# uzed-hmdi.net
KiCad netlist of a schematic drawn in EAGLE
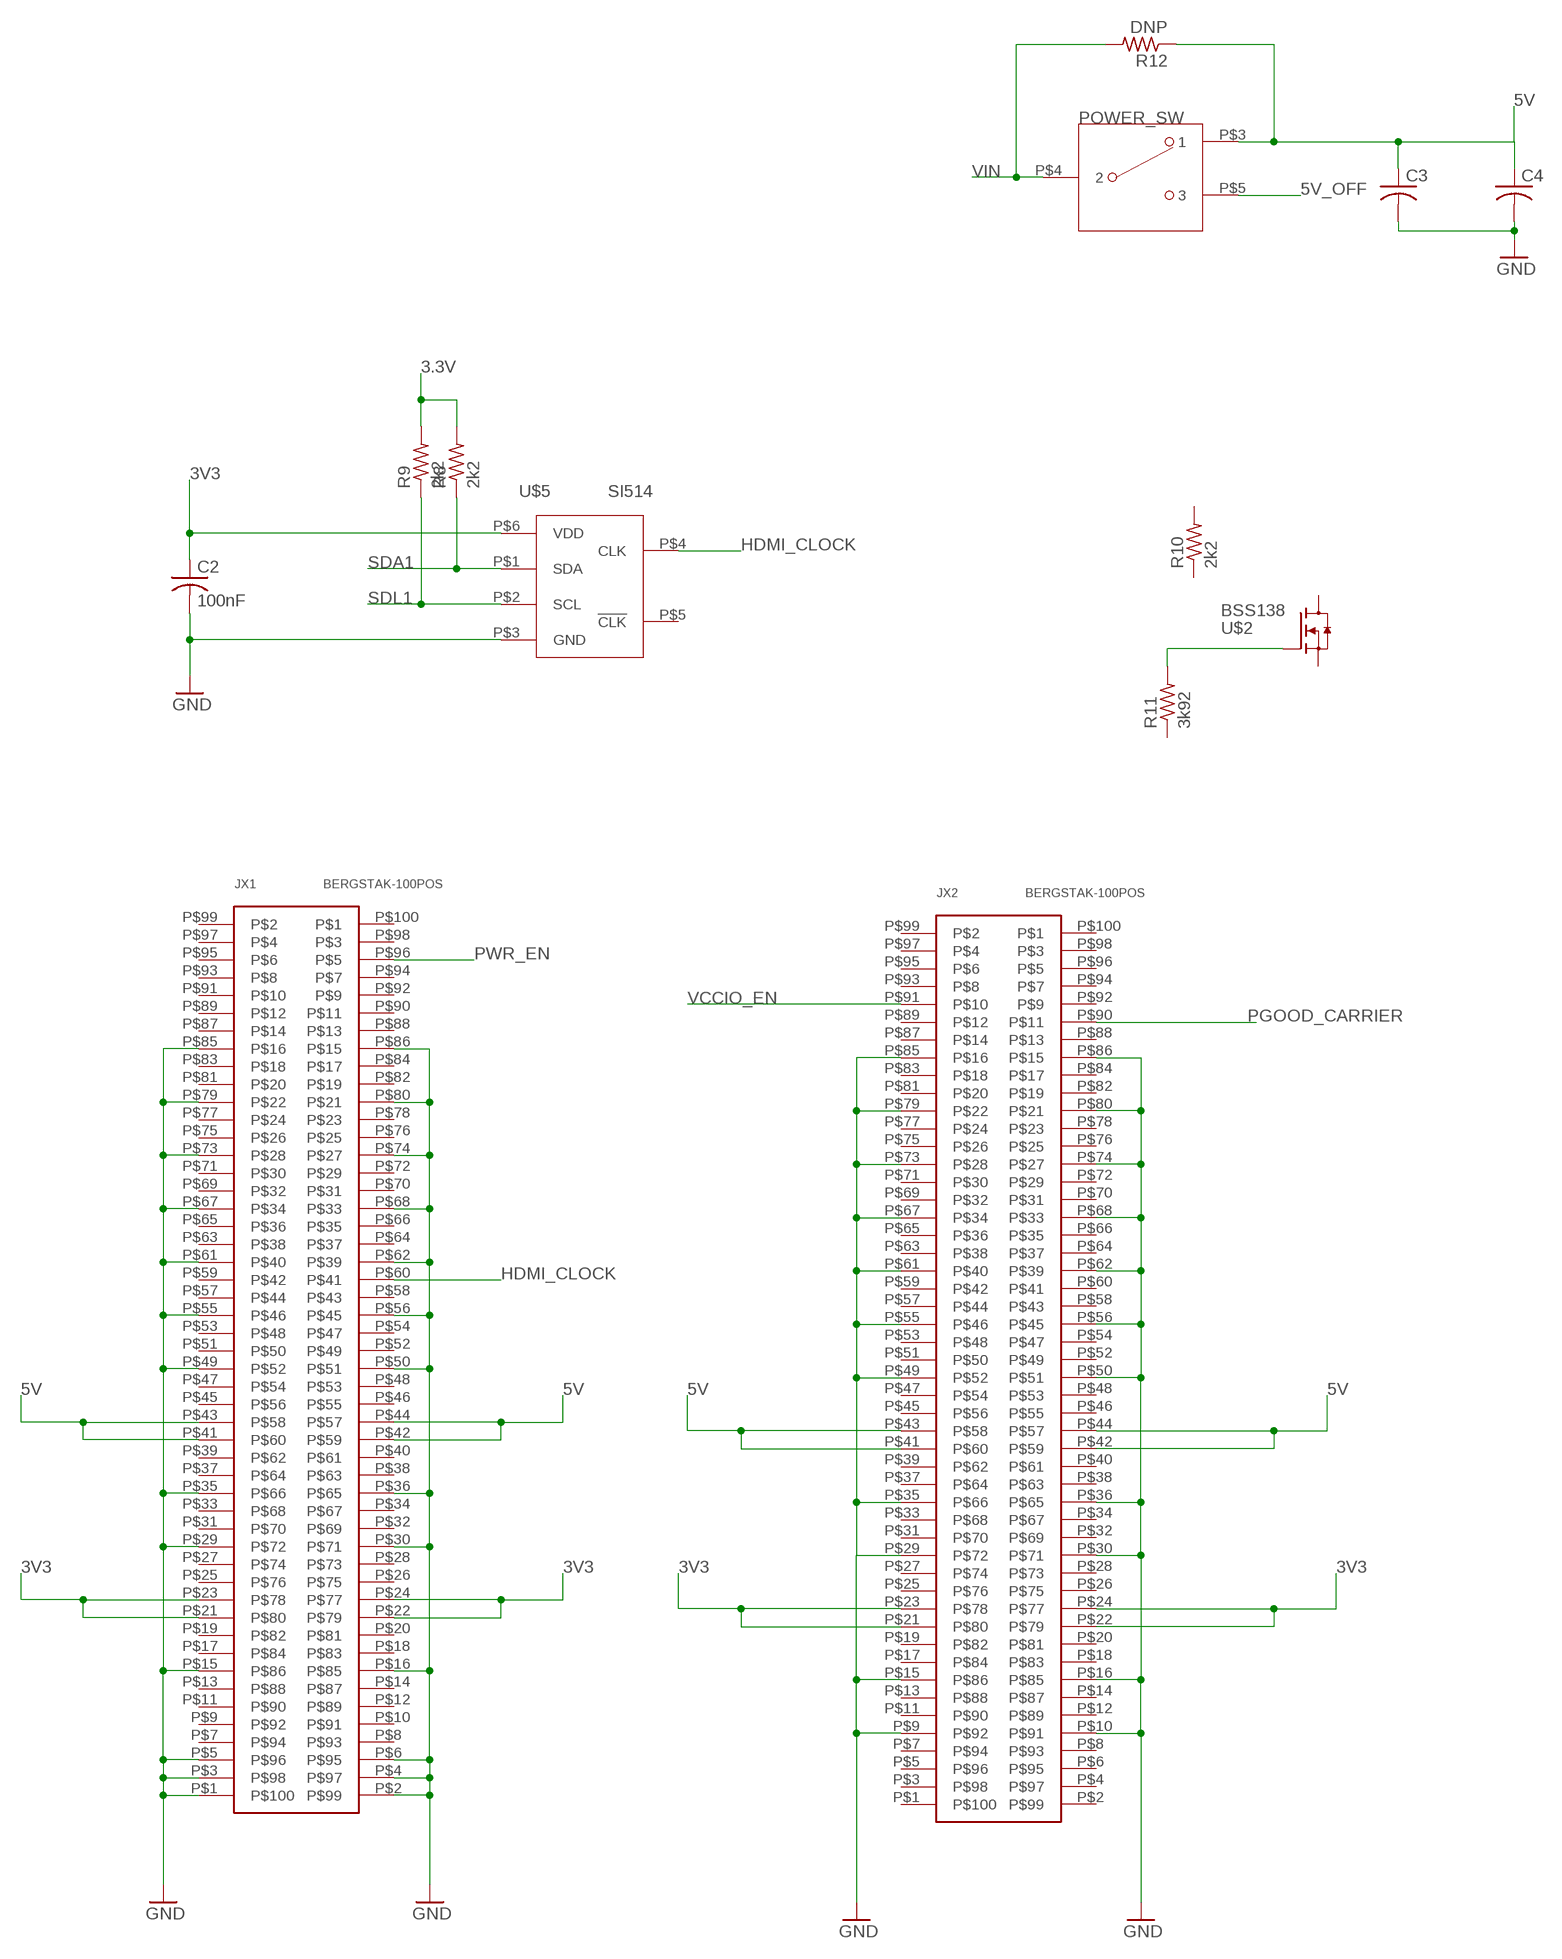
[diagram p0: schematic, sheet 1]
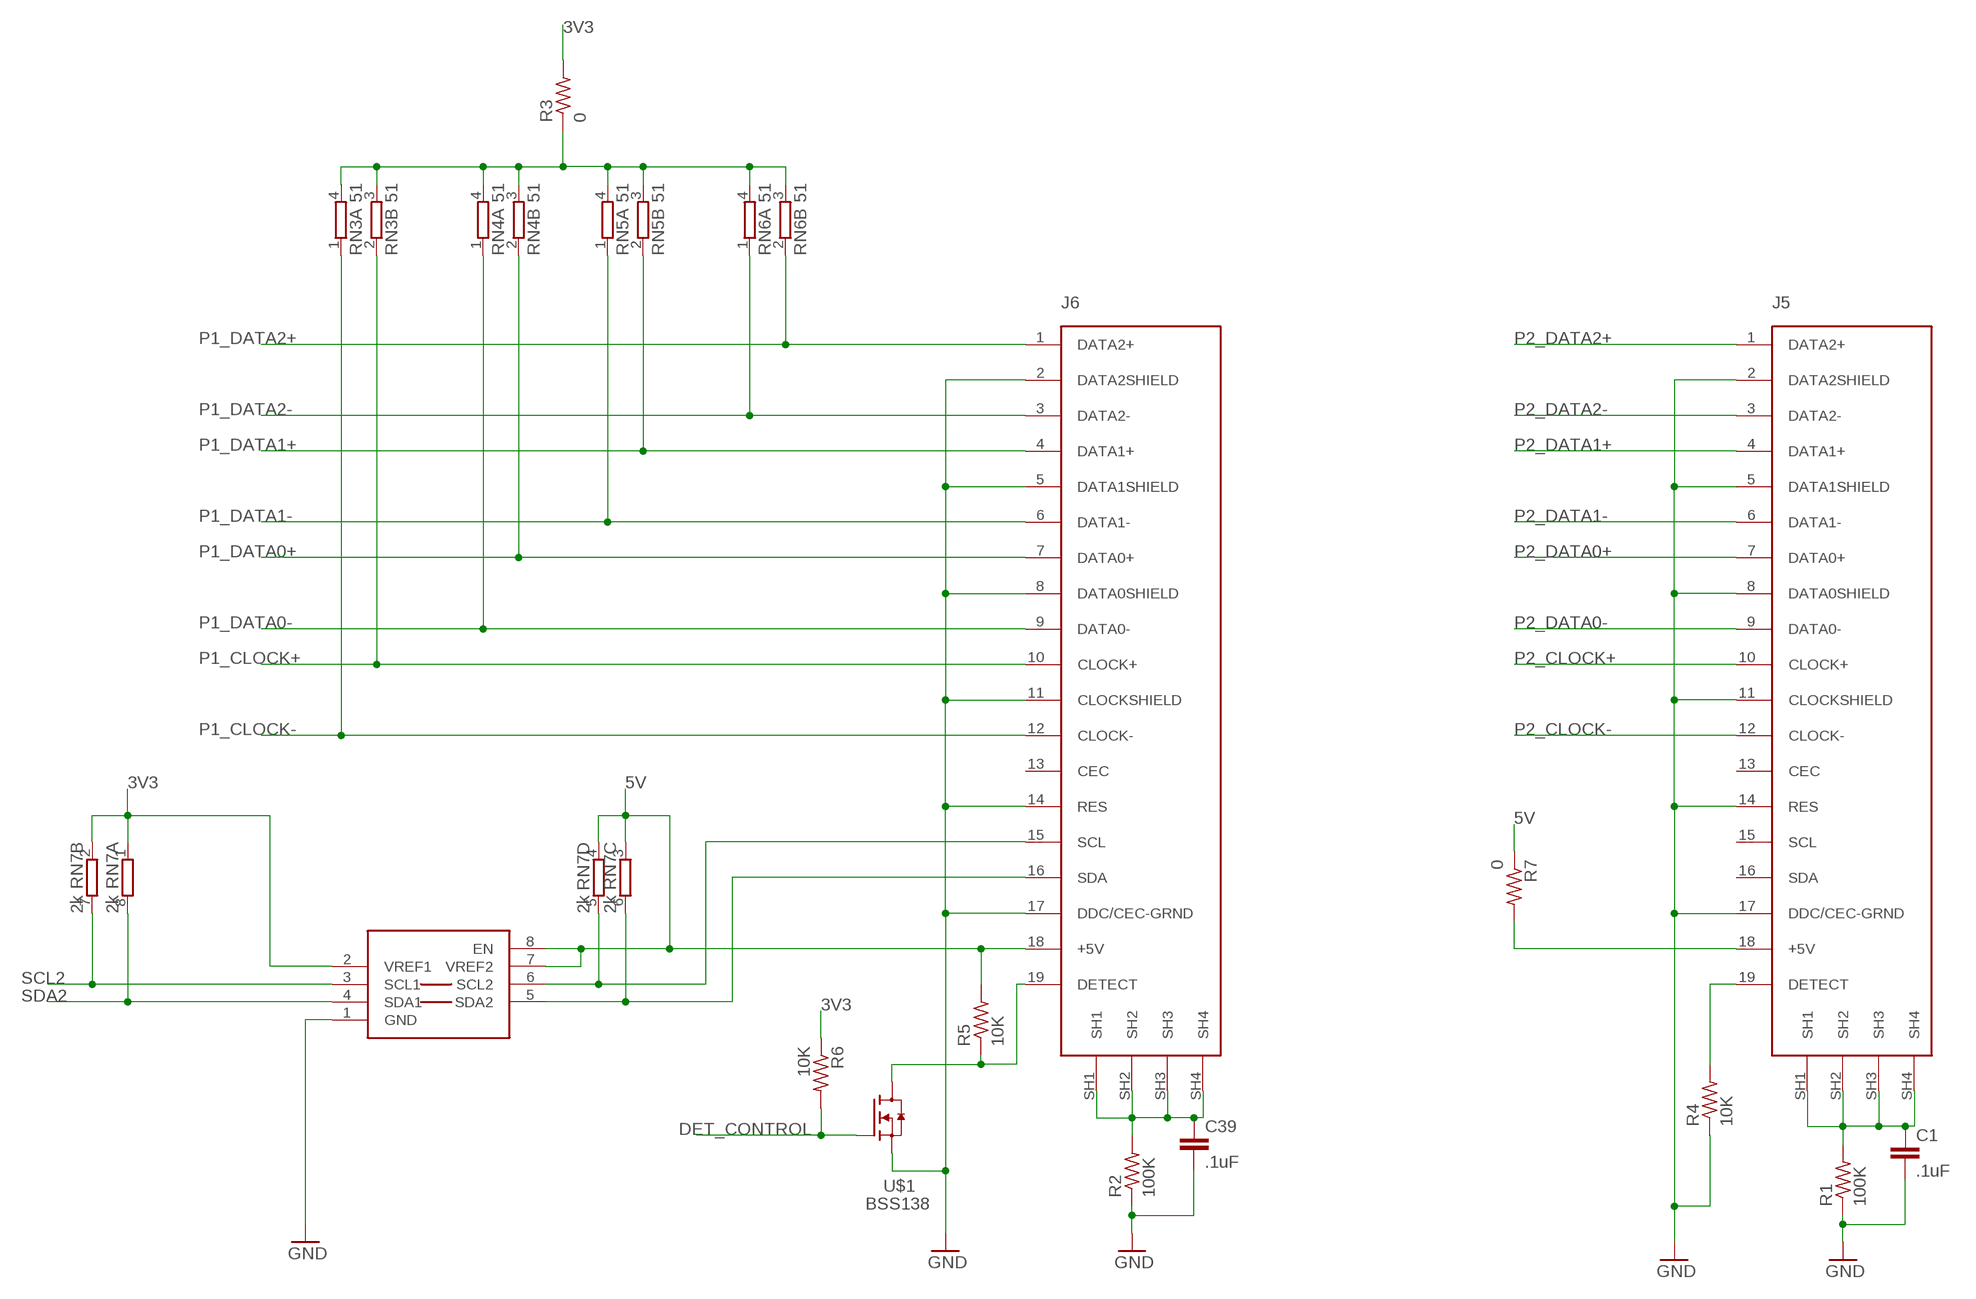
[diagram p1: schematic, sheet 2]

(export (version "E")
  (design (tool "Eeschema 10.0.6"))
  (components
    (comp (ref "C2")
      (value "100nF")
      (footprint "eagle-import:C0603")
      (libsource (lib "eagle-import") (part "C-USC0603"))
    )
    (comp (ref "C3")
      (value "C-USC0603")
      (footprint "eagle-import:C0603")
      (libsource (lib "eagle-import") (part "C-USC0603"))
    )
    (comp (ref "C4")
      (value "C-USC1206K")
      (footprint "eagle-import:C1206K")
      (libsource (lib "eagle-import") (part "C-USC1206K"))
    )
    (comp (ref "JX1")
      (value "BERGSTAK-100POS")
      (footprint "eagle-import:BERG100POS")
      (libsource (lib "eagle-import") (part "BERGSTAK-100POS"))
    )
    (comp (ref "JX2")
      (value "BERGSTAK-100POS")
      (footprint "eagle-import:BERG100POS")
      (libsource (lib "eagle-import") (part "BERGSTAK-100POS"))
    )
    (comp (ref "POWER_SW")
      (value "T511006")
      (footprint "eagle-import:SPDT")
      (libsource (lib "eagle-import") (part "T511006"))
    )
    (comp (ref "R8")
      (value "2k2")
      (footprint "eagle-import:R0603")
      (libsource (lib "eagle-import") (part "rcl_334_R-US_R0603"))
    )
    (comp (ref "R9")
      (value "2k2")
      (footprint "eagle-import:R0603")
      (libsource (lib "eagle-import") (part "rcl_334_R-US_R0603"))
    )
    (comp (ref "R10")
      (value "2k2")
      (footprint "eagle-import:R0603")
      (libsource (lib "eagle-import") (part "rcl_334_R-US_R0603"))
    )
    (comp (ref "R11")
      (value "3k92")
      (footprint "eagle-import:R0603")
      (libsource (lib "eagle-import") (part "rcl_334_R-US_R0603"))
    )
    (comp (ref "R12")
      (value "DNP")
      (footprint "eagle-import:R0603")
      (libsource (lib "eagle-import") (part "rcl_334_R-US_R0603"))
    )
    (comp (ref "U$2")
      (value "BSS138")
      (footprint "eagle-import:SOT23")
      (libsource (lib "eagle-import") (part "BSS138"))
    )
    (comp (ref "U$5")
      (value "SI514")
      (footprint "eagle-import:XTAL-6PIN")
      (libsource (lib "eagle-import") (part "SI514"))
    )
    (comp (ref "C1")
      (value ".1uF")
      (footprint "eagle-import:C0603K")
      (libsource (lib "eagle-import") (part "C-EUC0603K"))
    )
    (comp (ref "C39")
      (value ".1uF")
      (footprint "eagle-import:C0603K")
      (libsource (lib "eagle-import") (part "C-EUC0603K"))
    )
    (comp (ref "J5")
      (value "HDMI-TYPE-A-RECEPTICALFCI10029449")
      (footprint "eagle-import:FCI-HDMI-TYPE-A-RECEPT")
      (libsource (lib "eagle-import") (part "HDMI-TYPE-A-RECEPTICALFCI10029449"))
    )
    (comp (ref "J6")
      (value "HDMI-TYPE-A-RECEPTICALFCI10029449")
      (footprint "eagle-import:FCI-HDMI-TYPE-A-RECEPT")
      (libsource (lib "eagle-import") (part "HDMI-TYPE-A-RECEPTICALFCI10029449"))
    )
    (comp (ref "PCA9306")
      (value "PCA9306")
      (footprint "eagle-import:PSOP-8")
      (libsource (lib "eagle-import") (part "PCA9306"))
    )
    (comp (ref "R1")
      (value "100K")
      (footprint "eagle-import:R0603")
      (libsource (lib "eagle-import") (part "R-US_R0603"))
    )
    (comp (ref "R2")
      (value "100K")
      (footprint "eagle-import:R0603")
      (libsource (lib "eagle-import") (part "R-US_R0603"))
    )
    (comp (ref "R3")
      (value "0")
      (footprint "eagle-import:R0603")
      (libsource (lib "eagle-import") (part "rcl_334_R-US_R0603"))
    )
    (comp (ref "R4")
      (value "10K")
      (footprint "eagle-import:R0603")
      (libsource (lib "eagle-import") (part "R-US_R0603"))
    )
    (comp (ref "R5")
      (value "10K")
      (footprint "eagle-import:R0603")
      (libsource (lib "eagle-import") (part "R-US_R0603"))
    )
    (comp (ref "R6")
      (value "10K")
      (footprint "eagle-import:R0603")
      (libsource (lib "eagle-import") (part "R-US_R0603"))
    )
    (comp (ref "R7")
      (value "0")
      (footprint "eagle-import:R0603")
      (libsource (lib "eagle-import") (part "R-US_R0603"))
    )
    (comp (ref "RN3")
      (value "51")
      (footprint "eagle-import:EXB34V")
      (libsource (lib "eagle-import") (part "2R-NEXB34V"))
    )
    (comp (ref "RN4")
      (value "51")
      (footprint "eagle-import:EXB34V")
      (libsource (lib "eagle-import") (part "2R-NEXB34V"))
    )
    (comp (ref "RN5")
      (value "51")
      (footprint "eagle-import:EXB34V")
      (libsource (lib "eagle-import") (part "2R-NEXB34V"))
    )
    (comp (ref "RN6")
      (value "51")
      (footprint "eagle-import:EXB34V")
      (libsource (lib "eagle-import") (part "2R-NEXB34V"))
    )
    (comp (ref "RN7")
      (value "2k")
      (footprint "eagle-import:0603-ARV")
      (libsource (lib "eagle-import") (part "4R-N0603-ARV"))
    )
    (comp (ref "U$1")
      (value "BSS138")
      (footprint "eagle-import:SOT23")
      (libsource (lib "eagle-import") (part "BSS138"))
    )
  )
  (nets
    (net (code "1") (name "3.3V") (class "Default")
      (node (ref "R8") (pin "2") (pinfunction "2_2") (pintype "passive"))
      (node (ref "R9") (pin "2") (pinfunction "2_2") (pintype "passive"))
    )
    (net (code "2") (name "3V3") (class "Default")
      (node (ref "C2") (pin "1") (pinfunction "1_1") (pintype "passive"))
      (node (ref "JX1") (pin "P$21") (pinfunction "P$80_P$21") (pintype "bidirectional"))
      (node (ref "JX1") (pin "P$22") (pinfunction "P$79_P$22") (pintype "bidirectional"))
      (node (ref "JX1") (pin "P$23") (pinfunction "P$78_P$23") (pintype "bidirectional"))
      (node (ref "JX1") (pin "P$24") (pinfunction "P$77_P$24") (pintype "bidirectional"))
      (node (ref "JX2") (pin "P$21") (pinfunction "P$80_P$21") (pintype "bidirectional"))
      (node (ref "JX2") (pin "P$22") (pinfunction "P$79_P$22") (pintype "bidirectional"))
      (node (ref "JX2") (pin "P$23") (pinfunction "P$78_P$23") (pintype "bidirectional"))
      (node (ref "JX2") (pin "P$24") (pinfunction "P$77_P$24") (pintype "bidirectional"))
      (node (ref "PCA9306") (pin "2") (pinfunction "VREF1_2") (pintype "bidirectional"))
      (node (ref "R3") (pin "2") (pinfunction "2_2") (pintype "passive"))
      (node (ref "R6") (pin "1") (pinfunction "1_1") (pintype "passive"))
      (node (ref "RN7") (pin "1") (pinfunction "1_1") (pintype "passive"))
      (node (ref "RN7") (pin "2") (pinfunction "1_2") (pintype "passive"))
      (node (ref "U$5") (pin "P$6") (pinfunction "VDD_P$6") (pintype "bidirectional"))
    )
    (net (code "3") (name "5V") (class "Default")
      (node (ref "C3") (pin "1") (pinfunction "1_1") (pintype "passive"))
      (node (ref "C4") (pin "1") (pinfunction "1_1") (pintype "passive"))
      (node (ref "J6") (pin "18") (pinfunction "+5V_18") (pintype "bidirectional"))
      (node (ref "JX1") (pin "P$41") (pinfunction "P$60_P$41") (pintype "bidirectional"))
      (node (ref "JX1") (pin "P$42") (pinfunction "P$59_P$42") (pintype "bidirectional"))
      (node (ref "JX1") (pin "P$43") (pinfunction "P$58_P$43") (pintype "bidirectional"))
      (node (ref "JX1") (pin "P$44") (pinfunction "P$57_P$44") (pintype "bidirectional"))
      (node (ref "JX2") (pin "P$41") (pinfunction "P$60_P$41") (pintype "bidirectional"))
      (node (ref "JX2") (pin "P$42") (pinfunction "P$59_P$42") (pintype "bidirectional"))
      (node (ref "JX2") (pin "P$43") (pinfunction "P$58_P$43") (pintype "bidirectional"))
      (node (ref "JX2") (pin "P$44") (pinfunction "P$57_P$44") (pintype "bidirectional"))
      (node (ref "PCA9306") (pin "7") (pinfunction "VREF2_7") (pintype "bidirectional"))
      (node (ref "PCA9306") (pin "8") (pinfunction "EN_8") (pintype "bidirectional"))
      (node (ref "POWER_SW") (pin "P$3") (pinfunction "1_P$3") (pintype "bidirectional"))
      (node (ref "R12") (pin "1") (pinfunction "1_1") (pintype "passive"))
      (node (ref "R5") (pin "2") (pinfunction "2_2") (pintype "passive"))
      (node (ref "R7") (pin "1") (pinfunction "1_1") (pintype "passive"))
      (node (ref "RN7") (pin "3") (pinfunction "1_3") (pintype "passive"))
      (node (ref "RN7") (pin "4") (pinfunction "1_4") (pintype "passive"))
    )
    (net (code "4") (name "5V_OFF") (class "Default")
      (node (ref "POWER_SW") (pin "P$5") (pinfunction "3_P$5") (pintype "bidirectional"))
    )
    (net (code "5") (name "DET_CONTROL") (class "Default")
      (node (ref "R6") (pin "2") (pinfunction "2_2") (pintype "passive"))
      (node (ref "U$1") (pin "1") (pinfunction "G_1") (pintype "passive"))
    )
    (net (code "6") (name "GND") (class "Default")
      (node (ref "C1") (pin "2") (pinfunction "2_2") (pintype "passive"))
      (node (ref "C2") (pin "2") (pinfunction "2_2") (pintype "passive"))
      (node (ref "C3") (pin "2") (pinfunction "2_2") (pintype "passive"))
      (node (ref "C39") (pin "2") (pinfunction "2_2") (pintype "passive"))
      (node (ref "C4") (pin "2") (pinfunction "2_2") (pintype "passive"))
      (node (ref "J5") (pin "11") (pinfunction "CLOCKSHIELD_11") (pintype "bidirectional"))
      (node (ref "J5") (pin "14") (pinfunction "RES_14") (pintype "bidirectional"))
      (node (ref "J5") (pin "17") (pinfunction "DDC/CEC-GRND_17") (pintype "bidirectional"))
      (node (ref "J5") (pin "2") (pinfunction "DATA2SHIELD_2") (pintype "bidirectional"))
      (node (ref "J5") (pin "5") (pinfunction "DATA1SHIELD_5") (pintype "bidirectional"))
      (node (ref "J5") (pin "8") (pinfunction "DATA0SHIELD_8") (pintype "bidirectional"))
      (node (ref "J6") (pin "11") (pinfunction "CLOCKSHIELD_11") (pintype "bidirectional"))
      (node (ref "J6") (pin "14") (pinfunction "RES_14") (pintype "bidirectional"))
      (node (ref "J6") (pin "17") (pinfunction "DDC/CEC-GRND_17") (pintype "bidirectional"))
      (node (ref "J6") (pin "2") (pinfunction "DATA2SHIELD_2") (pintype "bidirectional"))
      (node (ref "J6") (pin "5") (pinfunction "DATA1SHIELD_5") (pintype "bidirectional"))
      (node (ref "J6") (pin "8") (pinfunction "DATA0SHIELD_8") (pintype "bidirectional"))
      (node (ref "JX1") (pin "P$1") (pinfunction "P$100_P$1") (pintype "bidirectional"))
      (node (ref "JX1") (pin "P$15") (pinfunction "P$86_P$15") (pintype "bidirectional"))
      (node (ref "JX1") (pin "P$16") (pinfunction "P$85_P$16") (pintype "bidirectional"))
      (node (ref "JX1") (pin "P$2") (pinfunction "P$99_P$2") (pintype "bidirectional"))
      (node (ref "JX1") (pin "P$29") (pinfunction "P$72_P$29") (pintype "bidirectional"))
      (node (ref "JX1") (pin "P$3") (pinfunction "P$98_P$3") (pintype "bidirectional"))
      (node (ref "JX1") (pin "P$30") (pinfunction "P$71_P$30") (pintype "bidirectional"))
      (node (ref "JX1") (pin "P$35") (pinfunction "P$66_P$35") (pintype "bidirectional"))
      (node (ref "JX1") (pin "P$36") (pinfunction "P$65_P$36") (pintype "bidirectional"))
      (node (ref "JX1") (pin "P$4") (pinfunction "P$97_P$4") (pintype "bidirectional"))
      (node (ref "JX1") (pin "P$49") (pinfunction "P$52_P$49") (pintype "bidirectional"))
      (node (ref "JX1") (pin "P$5") (pinfunction "P$96_P$5") (pintype "bidirectional"))
      (node (ref "JX1") (pin "P$50") (pinfunction "P$51_P$50") (pintype "bidirectional"))
      (node (ref "JX1") (pin "P$55") (pinfunction "P$46_P$55") (pintype "bidirectional"))
      (node (ref "JX1") (pin "P$56") (pinfunction "P$45_P$56") (pintype "bidirectional"))
      (node (ref "JX1") (pin "P$6") (pinfunction "P$95_P$6") (pintype "bidirectional"))
      (node (ref "JX1") (pin "P$61") (pinfunction "P$40_P$61") (pintype "bidirectional"))
      (node (ref "JX1") (pin "P$62") (pinfunction "P$39_P$62") (pintype "bidirectional"))
      (node (ref "JX1") (pin "P$67") (pinfunction "P$34_P$67") (pintype "bidirectional"))
      (node (ref "JX1") (pin "P$68") (pinfunction "P$33_P$68") (pintype "bidirectional"))
      (node (ref "JX1") (pin "P$73") (pinfunction "P$28_P$73") (pintype "bidirectional"))
      (node (ref "JX1") (pin "P$74") (pinfunction "P$27_P$74") (pintype "bidirectional"))
      (node (ref "JX1") (pin "P$79") (pinfunction "P$22_P$79") (pintype "bidirectional"))
      (node (ref "JX1") (pin "P$80") (pinfunction "P$21_P$80") (pintype "bidirectional"))
      (node (ref "JX1") (pin "P$85") (pinfunction "P$16_P$85") (pintype "bidirectional"))
      (node (ref "JX1") (pin "P$86") (pinfunction "P$15_P$86") (pintype "bidirectional"))
      (node (ref "JX2") (pin "P$10") (pinfunction "P$91_P$10") (pintype "bidirectional"))
      (node (ref "JX2") (pin "P$15") (pinfunction "P$86_P$15") (pintype "bidirectional"))
      (node (ref "JX2") (pin "P$16") (pinfunction "P$85_P$16") (pintype "bidirectional"))
      (node (ref "JX2") (pin "P$29") (pinfunction "P$72_P$29") (pintype "bidirectional"))
      (node (ref "JX2") (pin "P$30") (pinfunction "P$71_P$30") (pintype "bidirectional"))
      (node (ref "JX2") (pin "P$35") (pinfunction "P$66_P$35") (pintype "bidirectional"))
      (node (ref "JX2") (pin "P$36") (pinfunction "P$65_P$36") (pintype "bidirectional"))
      (node (ref "JX2") (pin "P$49") (pinfunction "P$52_P$49") (pintype "bidirectional"))
      (node (ref "JX2") (pin "P$50") (pinfunction "P$51_P$50") (pintype "bidirectional"))
      (node (ref "JX2") (pin "P$55") (pinfunction "P$46_P$55") (pintype "bidirectional"))
      (node (ref "JX2") (pin "P$56") (pinfunction "P$45_P$56") (pintype "bidirectional"))
      (node (ref "JX2") (pin "P$61") (pinfunction "P$40_P$61") (pintype "bidirectional"))
      (node (ref "JX2") (pin "P$62") (pinfunction "P$39_P$62") (pintype "bidirectional"))
      (node (ref "JX2") (pin "P$67") (pinfunction "P$34_P$67") (pintype "bidirectional"))
      (node (ref "JX2") (pin "P$68") (pinfunction "P$33_P$68") (pintype "bidirectional"))
      (node (ref "JX2") (pin "P$73") (pinfunction "P$28_P$73") (pintype "bidirectional"))
      (node (ref "JX2") (pin "P$74") (pinfunction "P$27_P$74") (pintype "bidirectional"))
      (node (ref "JX2") (pin "P$79") (pinfunction "P$22_P$79") (pintype "bidirectional"))
      (node (ref "JX2") (pin "P$80") (pinfunction "P$21_P$80") (pintype "bidirectional"))
      (node (ref "JX2") (pin "P$85") (pinfunction "P$16_P$85") (pintype "bidirectional"))
      (node (ref "JX2") (pin "P$86") (pinfunction "P$15_P$86") (pintype "bidirectional"))
      (node (ref "JX2") (pin "P$9") (pinfunction "P$92_P$9") (pintype "bidirectional"))
      (node (ref "PCA9306") (pin "1") (pinfunction "GND_1") (pintype "bidirectional"))
      (node (ref "R1") (pin "1") (pinfunction "1_1") (pintype "passive"))
      (node (ref "R2") (pin "1") (pinfunction "1_1") (pintype "passive"))
      (node (ref "R4") (pin "1") (pinfunction "1_1") (pintype "passive"))
      (node (ref "U$1") (pin "2") (pinfunction "S_2") (pintype "passive"))
      (node (ref "U$5") (pin "P$3") (pinfunction "GND_P$3") (pintype "bidirectional"))
    )
    (net (code "7") (name "HDMI_CLOCK") (class "Default")
      (node (ref "JX1") (pin "P$60") (pinfunction "P$41_P$60") (pintype "bidirectional"))
      (node (ref "U$5") (pin "P$4") (pinfunction "CLK_P$4") (pintype "bidirectional"))
    )
    (net (code "8") (name "Net-(C1-Pad1)") (class "Default")
      (node (ref "C1") (pin "1") (pinfunction "1_1") (pintype "passive"))
      (node (ref "J5") (pin "SH1") (pinfunction "SH1_SH1") (pintype "bidirectional"))
      (node (ref "J5") (pin "SH2") (pinfunction "SH2_SH2") (pintype "bidirectional"))
      (node (ref "J5") (pin "SH3") (pinfunction "SH3_SH3") (pintype "bidirectional"))
      (node (ref "J5") (pin "SH4") (pinfunction "SH4_SH4") (pintype "bidirectional"))
      (node (ref "R1") (pin "2") (pinfunction "2_2") (pintype "passive"))
    )
    (net (code "9") (name "Net-(C39-Pad1)") (class "Default")
      (node (ref "C39") (pin "1") (pinfunction "1_1") (pintype "passive"))
      (node (ref "J6") (pin "SH1") (pinfunction "SH1_SH1") (pintype "bidirectional"))
      (node (ref "J6") (pin "SH2") (pinfunction "SH2_SH2") (pintype "bidirectional"))
      (node (ref "J6") (pin "SH3") (pinfunction "SH3_SH3") (pintype "bidirectional"))
      (node (ref "J6") (pin "SH4") (pinfunction "SH4_SH4") (pintype "bidirectional"))
      (node (ref "R2") (pin "2") (pinfunction "2_2") (pintype "passive"))
    )
    (net (code "10") (name "Net-(J5-+5V)") (class "Default")
      (node (ref "J5") (pin "18") (pinfunction "+5V_18") (pintype "bidirectional"))
      (node (ref "R7") (pin "2") (pinfunction "2_2") (pintype "passive"))
    )
    (net (code "11") (name "Net-(J5-DETECT)") (class "Default")
      (node (ref "J5") (pin "19") (pinfunction "DETECT_19") (pintype "bidirectional"))
      (node (ref "R4") (pin "2") (pinfunction "2_2") (pintype "passive"))
    )
    (net (code "12") (name "Net-(J6-DETECT)") (class "Default")
      (node (ref "J6") (pin "19") (pinfunction "DETECT_19") (pintype "bidirectional"))
      (node (ref "R5") (pin "1") (pinfunction "1_1") (pintype "passive"))
      (node (ref "U$1") (pin "3") (pinfunction "D_3") (pintype "passive"))
    )
    (net (code "13") (name "Net-(J6-SCL)") (class "Default")
      (node (ref "J6") (pin "15") (pinfunction "SCL_15") (pintype "bidirectional"))
      (node (ref "PCA9306") (pin "6") (pinfunction "SCL2_6") (pintype "bidirectional"))
      (node (ref "RN7") (pin "5") (pinfunction "2_5") (pintype "passive"))
    )
    (net (code "14") (name "Net-(J6-SDA)") (class "Default")
      (node (ref "J6") (pin "16") (pinfunction "SDA_16") (pintype "bidirectional"))
      (node (ref "PCA9306") (pin "5") (pinfunction "SDA2_5") (pintype "bidirectional"))
      (node (ref "RN7") (pin "6") (pinfunction "2_6") (pintype "passive"))
    )
    (net (code "15") (name "Net-(RN3A-2)") (class "Default")
      (node (ref "R3") (pin "1") (pinfunction "1_1") (pintype "passive"))
      (node (ref "RN3") (pin "3") (pinfunction "2_3") (pintype "passive"))
      (node (ref "RN3") (pin "4") (pinfunction "2_4") (pintype "passive"))
      (node (ref "RN4") (pin "3") (pinfunction "2_3") (pintype "passive"))
      (node (ref "RN4") (pin "4") (pinfunction "2_4") (pintype "passive"))
      (node (ref "RN5") (pin "3") (pinfunction "2_3") (pintype "passive"))
      (node (ref "RN5") (pin "4") (pinfunction "2_4") (pintype "passive"))
      (node (ref "RN6") (pin "3") (pinfunction "2_3") (pintype "passive"))
      (node (ref "RN6") (pin "4") (pinfunction "2_4") (pintype "passive"))
    )
    (net (code "16") (name "Net-(U$2-G)") (class "Default")
      (node (ref "R11") (pin "2") (pinfunction "2_2") (pintype "passive"))
      (node (ref "U$2") (pin "1") (pinfunction "G_1") (pintype "passive"))
    )
    (net (code "17") (name "P1_CLOCK+") (class "Default")
      (node (ref "J6") (pin "10") (pinfunction "CLOCK+_10") (pintype "bidirectional"))
      (node (ref "RN3") (pin "2") (pinfunction "1_2") (pintype "passive"))
    )
    (net (code "18") (name "P1_CLOCK-") (class "Default")
      (node (ref "J6") (pin "12") (pinfunction "CLOCK-_12") (pintype "bidirectional"))
      (node (ref "RN3") (pin "1") (pinfunction "1_1") (pintype "passive"))
    )
    (net (code "19") (name "P1_DATA0+") (class "Default")
      (node (ref "J6") (pin "7") (pinfunction "DATA0+_7") (pintype "bidirectional"))
      (node (ref "RN4") (pin "2") (pinfunction "1_2") (pintype "passive"))
    )
    (net (code "20") (name "P1_DATA0-") (class "Default")
      (node (ref "J6") (pin "9") (pinfunction "DATA0-_9") (pintype "bidirectional"))
      (node (ref "RN4") (pin "1") (pinfunction "1_1") (pintype "passive"))
    )
    (net (code "21") (name "P1_DATA1+") (class "Default")
      (node (ref "J6") (pin "4") (pinfunction "DATA1+_4") (pintype "bidirectional"))
      (node (ref "RN5") (pin "2") (pinfunction "1_2") (pintype "passive"))
    )
    (net (code "22") (name "P1_DATA1-") (class "Default")
      (node (ref "J6") (pin "6") (pinfunction "DATA1-_6") (pintype "bidirectional"))
      (node (ref "RN5") (pin "1") (pinfunction "1_1") (pintype "passive"))
    )
    (net (code "23") (name "P1_DATA2+") (class "Default")
      (node (ref "J6") (pin "1") (pinfunction "DATA2+_1") (pintype "bidirectional"))
      (node (ref "RN6") (pin "2") (pinfunction "1_2") (pintype "passive"))
    )
    (net (code "24") (name "P1_DATA2-") (class "Default")
      (node (ref "J6") (pin "3") (pinfunction "DATA2-_3") (pintype "bidirectional"))
      (node (ref "RN6") (pin "1") (pinfunction "1_1") (pintype "passive"))
    )
    (net (code "25") (name "P2_CLOCK+") (class "Default")
      (node (ref "J5") (pin "10") (pinfunction "CLOCK+_10") (pintype "bidirectional"))
    )
    (net (code "26") (name "P2_CLOCK-") (class "Default")
      (node (ref "J5") (pin "12") (pinfunction "CLOCK-_12") (pintype "bidirectional"))
    )
    (net (code "27") (name "P2_DATA0+") (class "Default")
      (node (ref "J5") (pin "7") (pinfunction "DATA0+_7") (pintype "bidirectional"))
    )
    (net (code "28") (name "P2_DATA0-") (class "Default")
      (node (ref "J5") (pin "9") (pinfunction "DATA0-_9") (pintype "bidirectional"))
    )
    (net (code "29") (name "P2_DATA1+") (class "Default")
      (node (ref "J5") (pin "4") (pinfunction "DATA1+_4") (pintype "bidirectional"))
    )
    (net (code "30") (name "P2_DATA1-") (class "Default")
      (node (ref "J5") (pin "6") (pinfunction "DATA1-_6") (pintype "bidirectional"))
    )
    (net (code "31") (name "P2_DATA2+") (class "Default")
      (node (ref "J5") (pin "1") (pinfunction "DATA2+_1") (pintype "bidirectional"))
    )
    (net (code "32") (name "P2_DATA2-") (class "Default")
      (node (ref "J5") (pin "3") (pinfunction "DATA2-_3") (pintype "bidirectional"))
    )
    (net (code "33") (name "PGOOD_CARRIER") (class "Default")
      (node (ref "JX2") (pin "P$90") (pinfunction "P$11_P$90") (pintype "bidirectional"))
    )
    (net (code "34") (name "PWR_EN") (class "Default")
      (node (ref "JX1") (pin "P$96") (pinfunction "P$5_P$96") (pintype "bidirectional"))
    )
    (net (code "35") (name "SCL2") (class "Default")
      (node (ref "PCA9306") (pin "3") (pinfunction "SCL1_3") (pintype "bidirectional"))
      (node (ref "RN7") (pin "7") (pinfunction "2_7") (pintype "passive"))
    )
    (net (code "36") (name "SDA1") (class "Default")
      (node (ref "R8") (pin "1") (pinfunction "1_1") (pintype "passive"))
      (node (ref "U$5") (pin "P$1") (pinfunction "SDA_P$1") (pintype "bidirectional"))
    )
    (net (code "37") (name "SDA2") (class "Default")
      (node (ref "PCA9306") (pin "4") (pinfunction "SDA1_4") (pintype "bidirectional"))
      (node (ref "RN7") (pin "8") (pinfunction "2_8") (pintype "passive"))
    )
    (net (code "38") (name "SDL1") (class "Default")
      (node (ref "R9") (pin "1") (pinfunction "1_1") (pintype "passive"))
      (node (ref "U$5") (pin "P$2") (pinfunction "SCL_P$2") (pintype "bidirectional"))
    )
    (net (code "39") (name "VCCIO_EN") (class "Default")
      (node (ref "JX2") (pin "P$91") (pinfunction "P$10_P$91") (pintype "bidirectional"))
    )
    (net (code "40") (name "VIN") (class "Default")
      (node (ref "POWER_SW") (pin "P$4") (pinfunction "2_P$4") (pintype "bidirectional"))
      (node (ref "R12") (pin "2") (pinfunction "2_2") (pintype "passive"))
    )
    (net (code "41") (name "unconnected-(J5-CEC-Pad13)") (class "Default")
      (node (ref "J5") (pin "13") (pinfunction "CEC_13") (pintype "bidirectional"))
    )
    (net (code "42") (name "unconnected-(J5-SCL-Pad15)") (class "Default")
      (node (ref "J5") (pin "15") (pinfunction "SCL_15") (pintype "bidirectional"))
    )
    (net (code "43") (name "unconnected-(J5-SDA-Pad16)") (class "Default")
      (node (ref "J5") (pin "16") (pinfunction "SDA_16") (pintype "bidirectional"))
    )
    (net (code "44") (name "unconnected-(J6-CEC-Pad13)") (class "Default")
      (node (ref "J6") (pin "13") (pinfunction "CEC_13") (pintype "bidirectional"))
    )
    (net (code "45") (name "unconnected-(JX1-P$1-PadP$100)") (class "Default")
      (node (ref "JX1") (pin "P$100") (pinfunction "P$1_P$100") (pintype "bidirectional"))
    )
    (net (code "46") (name "unconnected-(JX1-P$2-PadP$99)") (class "Default")
      (node (ref "JX1") (pin "P$99") (pinfunction "P$2_P$99") (pintype "bidirectional"))
    )
    (net (code "47") (name "unconnected-(JX1-P$3-PadP$98)") (class "Default")
      (node (ref "JX1") (pin "P$98") (pinfunction "P$3_P$98") (pintype "bidirectional"))
    )
    (net (code "48") (name "unconnected-(JX1-P$4-PadP$97)") (class "Default")
      (node (ref "JX1") (pin "P$97") (pinfunction "P$4_P$97") (pintype "bidirectional"))
    )
    (net (code "49") (name "unconnected-(JX1-P$6-PadP$95)") (class "Default")
      (node (ref "JX1") (pin "P$95") (pinfunction "P$6_P$95") (pintype "bidirectional"))
    )
    (net (code "50") (name "unconnected-(JX1-P$7-PadP$94)") (class "Default")
      (node (ref "JX1") (pin "P$94") (pinfunction "P$7_P$94") (pintype "bidirectional"))
    )
    (net (code "51") (name "unconnected-(JX1-P$8-PadP$93)") (class "Default")
      (node (ref "JX1") (pin "P$93") (pinfunction "P$8_P$93") (pintype "bidirectional"))
    )
    (net (code "52") (name "unconnected-(JX1-P$9-PadP$92)") (class "Default")
      (node (ref "JX1") (pin "P$92") (pinfunction "P$9_P$92") (pintype "bidirectional"))
    )
    (net (code "53") (name "unconnected-(JX1-P$10-PadP$91)") (class "Default")
      (node (ref "JX1") (pin "P$91") (pinfunction "P$10_P$91") (pintype "bidirectional"))
    )
    (net (code "54") (name "unconnected-(JX1-P$11-PadP$90)") (class "Default")
      (node (ref "JX1") (pin "P$90") (pinfunction "P$11_P$90") (pintype "bidirectional"))
    )
    (net (code "55") (name "unconnected-(JX1-P$12-PadP$89)") (class "Default")
      (node (ref "JX1") (pin "P$89") (pinfunction "P$12_P$89") (pintype "bidirectional"))
    )
    (net (code "56") (name "unconnected-(JX1-P$13-PadP$88)") (class "Default")
      (node (ref "JX1") (pin "P$88") (pinfunction "P$13_P$88") (pintype "bidirectional"))
    )
    (net (code "57") (name "unconnected-(JX1-P$14-PadP$87)") (class "Default")
      (node (ref "JX1") (pin "P$87") (pinfunction "P$14_P$87") (pintype "bidirectional"))
    )
    (net (code "58") (name "unconnected-(JX1-P$17-PadP$84)") (class "Default")
      (node (ref "JX1") (pin "P$84") (pinfunction "P$17_P$84") (pintype "bidirectional"))
    )
    (net (code "59") (name "unconnected-(JX1-P$18-PadP$83)") (class "Default")
      (node (ref "JX1") (pin "P$83") (pinfunction "P$18_P$83") (pintype "bidirectional"))
    )
    (net (code "60") (name "unconnected-(JX1-P$19-PadP$82)") (class "Default")
      (node (ref "JX1") (pin "P$82") (pinfunction "P$19_P$82") (pintype "bidirectional"))
    )
    (net (code "61") (name "unconnected-(JX1-P$20-PadP$81)") (class "Default")
      (node (ref "JX1") (pin "P$81") (pinfunction "P$20_P$81") (pintype "bidirectional"))
    )
    (net (code "62") (name "unconnected-(JX1-P$23-PadP$78)") (class "Default")
      (node (ref "JX1") (pin "P$78") (pinfunction "P$23_P$78") (pintype "bidirectional"))
    )
    (net (code "63") (name "unconnected-(JX1-P$24-PadP$77)") (class "Default")
      (node (ref "JX1") (pin "P$77") (pinfunction "P$24_P$77") (pintype "bidirectional"))
    )
    (net (code "64") (name "unconnected-(JX1-P$25-PadP$76)") (class "Default")
      (node (ref "JX1") (pin "P$76") (pinfunction "P$25_P$76") (pintype "bidirectional"))
    )
    (net (code "65") (name "unconnected-(JX1-P$26-PadP$75)") (class "Default")
      (node (ref "JX1") (pin "P$75") (pinfunction "P$26_P$75") (pintype "bidirectional"))
    )
    (net (code "66") (name "unconnected-(JX1-P$29-PadP$72)") (class "Default")
      (node (ref "JX1") (pin "P$72") (pinfunction "P$29_P$72") (pintype "bidirectional"))
    )
    (net (code "67") (name "unconnected-(JX1-P$30-PadP$71)") (class "Default")
      (node (ref "JX1") (pin "P$71") (pinfunction "P$30_P$71") (pintype "bidirectional"))
    )
    (net (code "68") (name "unconnected-(JX1-P$31-PadP$70)") (class "Default")
      (node (ref "JX1") (pin "P$70") (pinfunction "P$31_P$70") (pintype "bidirectional"))
    )
    (net (code "69") (name "unconnected-(JX1-P$32-PadP$69)") (class "Default")
      (node (ref "JX1") (pin "P$69") (pinfunction "P$32_P$69") (pintype "bidirectional"))
    )
    (net (code "70") (name "unconnected-(JX1-P$35-PadP$66)") (class "Default")
      (node (ref "JX1") (pin "P$66") (pinfunction "P$35_P$66") (pintype "bidirectional"))
    )
    (net (code "71") (name "unconnected-(JX1-P$36-PadP$65)") (class "Default")
      (node (ref "JX1") (pin "P$65") (pinfunction "P$36_P$65") (pintype "bidirectional"))
    )
    (net (code "72") (name "unconnected-(JX1-P$37-PadP$64)") (class "Default")
      (node (ref "JX1") (pin "P$64") (pinfunction "P$37_P$64") (pintype "bidirectional"))
    )
    (net (code "73") (name "unconnected-(JX1-P$38-PadP$63)") (class "Default")
      (node (ref "JX1") (pin "P$63") (pinfunction "P$38_P$63") (pintype "bidirectional"))
    )
    (net (code "74") (name "unconnected-(JX1-P$42-PadP$59)") (class "Default")
      (node (ref "JX1") (pin "P$59") (pinfunction "P$42_P$59") (pintype "bidirectional"))
    )
    (net (code "75") (name "unconnected-(JX1-P$43-PadP$58)") (class "Default")
      (node (ref "JX1") (pin "P$58") (pinfunction "P$43_P$58") (pintype "bidirectional"))
    )
    (net (code "76") (name "unconnected-(JX1-P$44-PadP$57)") (class "Default")
      (node (ref "JX1") (pin "P$57") (pinfunction "P$44_P$57") (pintype "bidirectional"))
    )
    (net (code "77") (name "unconnected-(JX1-P$47-PadP$54)") (class "Default")
      (node (ref "JX1") (pin "P$54") (pinfunction "P$47_P$54") (pintype "bidirectional"))
    )
    (net (code "78") (name "unconnected-(JX1-P$48-PadP$53)") (class "Default")
      (node (ref "JX1") (pin "P$53") (pinfunction "P$48_P$53") (pintype "bidirectional"))
    )
    (net (code "79") (name "unconnected-(JX1-P$49-PadP$52)") (class "Default")
      (node (ref "JX1") (pin "P$52") (pinfunction "P$49_P$52") (pintype "bidirectional"))
    )
    (net (code "80") (name "unconnected-(JX1-P$50-PadP$51)") (class "Default")
      (node (ref "JX1") (pin "P$51") (pinfunction "P$50_P$51") (pintype "bidirectional"))
    )
    (net (code "81") (name "unconnected-(JX1-P$53-PadP$48)") (class "Default")
      (node (ref "JX1") (pin "P$48") (pinfunction "P$53_P$48") (pintype "bidirectional"))
    )
    (net (code "82") (name "unconnected-(JX1-P$54-PadP$47)") (class "Default")
      (node (ref "JX1") (pin "P$47") (pinfunction "P$54_P$47") (pintype "bidirectional"))
    )
    (net (code "83") (name "unconnected-(JX1-P$55-PadP$46)") (class "Default")
      (node (ref "JX1") (pin "P$46") (pinfunction "P$55_P$46") (pintype "bidirectional"))
    )
    (net (code "84") (name "unconnected-(JX1-P$56-PadP$45)") (class "Default")
      (node (ref "JX1") (pin "P$45") (pinfunction "P$56_P$45") (pintype "bidirectional"))
    )
    (net (code "85") (name "unconnected-(JX1-P$61-PadP$40)") (class "Default")
      (node (ref "JX1") (pin "P$40") (pinfunction "P$61_P$40") (pintype "bidirectional"))
    )
    (net (code "86") (name "unconnected-(JX1-P$62-PadP$39)") (class "Default")
      (node (ref "JX1") (pin "P$39") (pinfunction "P$62_P$39") (pintype "bidirectional"))
    )
    (net (code "87") (name "unconnected-(JX1-P$63-PadP$38)") (class "Default")
      (node (ref "JX1") (pin "P$38") (pinfunction "P$63_P$38") (pintype "bidirectional"))
    )
    (net (code "88") (name "unconnected-(JX1-P$64-PadP$37)") (class "Default")
      (node (ref "JX1") (pin "P$37") (pinfunction "P$64_P$37") (pintype "bidirectional"))
    )
    (net (code "89") (name "unconnected-(JX1-P$67-PadP$34)") (class "Default")
      (node (ref "JX1") (pin "P$34") (pinfunction "P$67_P$34") (pintype "bidirectional"))
    )
    (net (code "90") (name "unconnected-(JX1-P$68-PadP$33)") (class "Default")
      (node (ref "JX1") (pin "P$33") (pinfunction "P$68_P$33") (pintype "bidirectional"))
    )
    (net (code "91") (name "unconnected-(JX1-P$69-PadP$32)") (class "Default")
      (node (ref "JX1") (pin "P$32") (pinfunction "P$69_P$32") (pintype "bidirectional"))
    )
    (net (code "92") (name "unconnected-(JX1-P$70-PadP$31)") (class "Default")
      (node (ref "JX1") (pin "P$31") (pinfunction "P$70_P$31") (pintype "bidirectional"))
    )
    (net (code "93") (name "unconnected-(JX1-P$73-PadP$28)") (class "Default")
      (node (ref "JX1") (pin "P$28") (pinfunction "P$73_P$28") (pintype "bidirectional"))
    )
    (net (code "94") (name "unconnected-(JX1-P$74-PadP$27)") (class "Default")
      (node (ref "JX1") (pin "P$27") (pinfunction "P$74_P$27") (pintype "bidirectional"))
    )
    (net (code "95") (name "unconnected-(JX1-P$75-PadP$26)") (class "Default")
      (node (ref "JX1") (pin "P$26") (pinfunction "P$75_P$26") (pintype "bidirectional"))
    )
    (net (code "96") (name "unconnected-(JX1-P$76-PadP$25)") (class "Default")
      (node (ref "JX1") (pin "P$25") (pinfunction "P$76_P$25") (pintype "bidirectional"))
    )
    (net (code "97") (name "unconnected-(JX1-P$81-PadP$20)") (class "Default")
      (node (ref "JX1") (pin "P$20") (pinfunction "P$81_P$20") (pintype "bidirectional"))
    )
    (net (code "98") (name "unconnected-(JX1-P$82-PadP$19)") (class "Default")
      (node (ref "JX1") (pin "P$19") (pinfunction "P$82_P$19") (pintype "bidirectional"))
    )
    (net (code "99") (name "unconnected-(JX1-P$83-PadP$18)") (class "Default")
      (node (ref "JX1") (pin "P$18") (pinfunction "P$83_P$18") (pintype "bidirectional"))
    )
    (net (code "100") (name "unconnected-(JX1-P$84-PadP$17)") (class "Default")
      (node (ref "JX1") (pin "P$17") (pinfunction "P$84_P$17") (pintype "bidirectional"))
    )
    (net (code "101") (name "unconnected-(JX1-P$87-PadP$14)") (class "Default")
      (node (ref "JX1") (pin "P$14") (pinfunction "P$87_P$14") (pintype "bidirectional"))
    )
    (net (code "102") (name "unconnected-(JX1-P$88-PadP$13)") (class "Default")
      (node (ref "JX1") (pin "P$13") (pinfunction "P$88_P$13") (pintype "bidirectional"))
    )
    (net (code "103") (name "unconnected-(JX1-P$89-PadP$12)") (class "Default")
      (node (ref "JX1") (pin "P$12") (pinfunction "P$89_P$12") (pintype "bidirectional"))
    )
    (net (code "104") (name "unconnected-(JX1-P$90-PadP$11)") (class "Default")
      (node (ref "JX1") (pin "P$11") (pinfunction "P$90_P$11") (pintype "bidirectional"))
    )
    (net (code "105") (name "unconnected-(JX1-P$91-PadP$10)") (class "Default")
      (node (ref "JX1") (pin "P$10") (pinfunction "P$91_P$10") (pintype "bidirectional"))
    )
    (net (code "106") (name "unconnected-(JX1-P$92-PadP$9)") (class "Default")
      (node (ref "JX1") (pin "P$9") (pinfunction "P$92_P$9") (pintype "bidirectional"))
    )
    (net (code "107") (name "unconnected-(JX1-P$93-PadP$8)") (class "Default")
      (node (ref "JX1") (pin "P$8") (pinfunction "P$93_P$8") (pintype "bidirectional"))
    )
    (net (code "108") (name "unconnected-(JX1-P$94-PadP$7)") (class "Default")
      (node (ref "JX1") (pin "P$7") (pinfunction "P$94_P$7") (pintype "bidirectional"))
    )
    (net (code "109") (name "unconnected-(JX2-P$1-PadP$100)") (class "Default")
      (node (ref "JX2") (pin "P$100") (pinfunction "P$1_P$100") (pintype "bidirectional"))
    )
    (net (code "110") (name "unconnected-(JX2-P$2-PadP$99)") (class "Default")
      (node (ref "JX2") (pin "P$99") (pinfunction "P$2_P$99") (pintype "bidirectional"))
    )
    (net (code "111") (name "unconnected-(JX2-P$3-PadP$98)") (class "Default")
      (node (ref "JX2") (pin "P$98") (pinfunction "P$3_P$98") (pintype "bidirectional"))
    )
    (net (code "112") (name "unconnected-(JX2-P$4-PadP$97)") (class "Default")
      (node (ref "JX2") (pin "P$97") (pinfunction "P$4_P$97") (pintype "bidirectional"))
    )
    (net (code "113") (name "unconnected-(JX2-P$5-PadP$96)") (class "Default")
      (node (ref "JX2") (pin "P$96") (pinfunction "P$5_P$96") (pintype "bidirectional"))
    )
    (net (code "114") (name "unconnected-(JX2-P$6-PadP$95)") (class "Default")
      (node (ref "JX2") (pin "P$95") (pinfunction "P$6_P$95") (pintype "bidirectional"))
    )
    (net (code "115") (name "unconnected-(JX2-P$7-PadP$94)") (class "Default")
      (node (ref "JX2") (pin "P$94") (pinfunction "P$7_P$94") (pintype "bidirectional"))
    )
    (net (code "116") (name "unconnected-(JX2-P$8-PadP$93)") (class "Default")
      (node (ref "JX2") (pin "P$93") (pinfunction "P$8_P$93") (pintype "bidirectional"))
    )
    (net (code "117") (name "unconnected-(JX2-P$9-PadP$92)") (class "Default")
      (node (ref "JX2") (pin "P$92") (pinfunction "P$9_P$92") (pintype "bidirectional"))
    )
    (net (code "118") (name "unconnected-(JX2-P$12-PadP$89)") (class "Default")
      (node (ref "JX2") (pin "P$89") (pinfunction "P$12_P$89") (pintype "bidirectional"))
    )
    (net (code "119") (name "unconnected-(JX2-P$13-PadP$88)") (class "Default")
      (node (ref "JX2") (pin "P$88") (pinfunction "P$13_P$88") (pintype "bidirectional"))
    )
    (net (code "120") (name "unconnected-(JX2-P$14-PadP$87)") (class "Default")
      (node (ref "JX2") (pin "P$87") (pinfunction "P$14_P$87") (pintype "bidirectional"))
    )
    (net (code "121") (name "unconnected-(JX2-P$17-PadP$84)") (class "Default")
      (node (ref "JX2") (pin "P$84") (pinfunction "P$17_P$84") (pintype "bidirectional"))
    )
    (net (code "122") (name "unconnected-(JX2-P$18-PadP$83)") (class "Default")
      (node (ref "JX2") (pin "P$83") (pinfunction "P$18_P$83") (pintype "bidirectional"))
    )
    (net (code "123") (name "unconnected-(JX2-P$19-PadP$82)") (class "Default")
      (node (ref "JX2") (pin "P$82") (pinfunction "P$19_P$82") (pintype "bidirectional"))
    )
    (net (code "124") (name "unconnected-(JX2-P$20-PadP$81)") (class "Default")
      (node (ref "JX2") (pin "P$81") (pinfunction "P$20_P$81") (pintype "bidirectional"))
    )
    (net (code "125") (name "unconnected-(JX2-P$23-PadP$78)") (class "Default")
      (node (ref "JX2") (pin "P$78") (pinfunction "P$23_P$78") (pintype "bidirectional"))
    )
    (net (code "126") (name "unconnected-(JX2-P$24-PadP$77)") (class "Default")
      (node (ref "JX2") (pin "P$77") (pinfunction "P$24_P$77") (pintype "bidirectional"))
    )
    (net (code "127") (name "unconnected-(JX2-P$25-PadP$76)") (class "Default")
      (node (ref "JX2") (pin "P$76") (pinfunction "P$25_P$76") (pintype "bidirectional"))
    )
    (net (code "128") (name "unconnected-(JX2-P$26-PadP$75)") (class "Default")
      (node (ref "JX2") (pin "P$75") (pinfunction "P$26_P$75") (pintype "bidirectional"))
    )
    (net (code "129") (name "unconnected-(JX2-P$29-PadP$72)") (class "Default")
      (node (ref "JX2") (pin "P$72") (pinfunction "P$29_P$72") (pintype "bidirectional"))
    )
    (net (code "130") (name "unconnected-(JX2-P$30-PadP$71)") (class "Default")
      (node (ref "JX2") (pin "P$71") (pinfunction "P$30_P$71") (pintype "bidirectional"))
    )
    (net (code "131") (name "unconnected-(JX2-P$31-PadP$70)") (class "Default")
      (node (ref "JX2") (pin "P$70") (pinfunction "P$31_P$70") (pintype "bidirectional"))
    )
    (net (code "132") (name "unconnected-(JX2-P$32-PadP$69)") (class "Default")
      (node (ref "JX2") (pin "P$69") (pinfunction "P$32_P$69") (pintype "bidirectional"))
    )
    (net (code "133") (name "unconnected-(JX2-P$35-PadP$66)") (class "Default")
      (node (ref "JX2") (pin "P$66") (pinfunction "P$35_P$66") (pintype "bidirectional"))
    )
    (net (code "134") (name "unconnected-(JX2-P$36-PadP$65)") (class "Default")
      (node (ref "JX2") (pin "P$65") (pinfunction "P$36_P$65") (pintype "bidirectional"))
    )
    (net (code "135") (name "unconnected-(JX2-P$37-PadP$64)") (class "Default")
      (node (ref "JX2") (pin "P$64") (pinfunction "P$37_P$64") (pintype "bidirectional"))
    )
    (net (code "136") (name "unconnected-(JX2-P$38-PadP$63)") (class "Default")
      (node (ref "JX2") (pin "P$63") (pinfunction "P$38_P$63") (pintype "bidirectional"))
    )
    (net (code "137") (name "unconnected-(JX2-P$41-PadP$60)") (class "Default")
      (node (ref "JX2") (pin "P$60") (pinfunction "P$41_P$60") (pintype "bidirectional"))
    )
    (net (code "138") (name "unconnected-(JX2-P$42-PadP$59)") (class "Default")
      (node (ref "JX2") (pin "P$59") (pinfunction "P$42_P$59") (pintype "bidirectional"))
    )
    (net (code "139") (name "unconnected-(JX2-P$43-PadP$58)") (class "Default")
      (node (ref "JX2") (pin "P$58") (pinfunction "P$43_P$58") (pintype "bidirectional"))
    )
    (net (code "140") (name "unconnected-(JX2-P$44-PadP$57)") (class "Default")
      (node (ref "JX2") (pin "P$57") (pinfunction "P$44_P$57") (pintype "bidirectional"))
    )
    (net (code "141") (name "unconnected-(JX2-P$47-PadP$54)") (class "Default")
      (node (ref "JX2") (pin "P$54") (pinfunction "P$47_P$54") (pintype "bidirectional"))
    )
    (net (code "142") (name "unconnected-(JX2-P$48-PadP$53)") (class "Default")
      (node (ref "JX2") (pin "P$53") (pinfunction "P$48_P$53") (pintype "bidirectional"))
    )
    (net (code "143") (name "unconnected-(JX2-P$49-PadP$52)") (class "Default")
      (node (ref "JX2") (pin "P$52") (pinfunction "P$49_P$52") (pintype "bidirectional"))
    )
    (net (code "144") (name "unconnected-(JX2-P$50-PadP$51)") (class "Default")
      (node (ref "JX2") (pin "P$51") (pinfunction "P$50_P$51") (pintype "bidirectional"))
    )
    (net (code "145") (name "unconnected-(JX2-P$53-PadP$48)") (class "Default")
      (node (ref "JX2") (pin "P$48") (pinfunction "P$53_P$48") (pintype "bidirectional"))
    )
    (net (code "146") (name "unconnected-(JX2-P$54-PadP$47)") (class "Default")
      (node (ref "JX2") (pin "P$47") (pinfunction "P$54_P$47") (pintype "bidirectional"))
    )
    (net (code "147") (name "unconnected-(JX2-P$55-PadP$46)") (class "Default")
      (node (ref "JX2") (pin "P$46") (pinfunction "P$55_P$46") (pintype "bidirectional"))
    )
    (net (code "148") (name "unconnected-(JX2-P$56-PadP$45)") (class "Default")
      (node (ref "JX2") (pin "P$45") (pinfunction "P$56_P$45") (pintype "bidirectional"))
    )
    (net (code "149") (name "unconnected-(JX2-P$61-PadP$40)") (class "Default")
      (node (ref "JX2") (pin "P$40") (pinfunction "P$61_P$40") (pintype "bidirectional"))
    )
    (net (code "150") (name "unconnected-(JX2-P$62-PadP$39)") (class "Default")
      (node (ref "JX2") (pin "P$39") (pinfunction "P$62_P$39") (pintype "bidirectional"))
    )
    (net (code "151") (name "unconnected-(JX2-P$63-PadP$38)") (class "Default")
      (node (ref "JX2") (pin "P$38") (pinfunction "P$63_P$38") (pintype "bidirectional"))
    )
    (net (code "152") (name "unconnected-(JX2-P$64-PadP$37)") (class "Default")
      (node (ref "JX2") (pin "P$37") (pinfunction "P$64_P$37") (pintype "bidirectional"))
    )
    (net (code "153") (name "unconnected-(JX2-P$67-PadP$34)") (class "Default")
      (node (ref "JX2") (pin "P$34") (pinfunction "P$67_P$34") (pintype "bidirectional"))
    )
    (net (code "154") (name "unconnected-(JX2-P$68-PadP$33)") (class "Default")
      (node (ref "JX2") (pin "P$33") (pinfunction "P$68_P$33") (pintype "bidirectional"))
    )
    (net (code "155") (name "unconnected-(JX2-P$69-PadP$32)") (class "Default")
      (node (ref "JX2") (pin "P$32") (pinfunction "P$69_P$32") (pintype "bidirectional"))
    )
    (net (code "156") (name "unconnected-(JX2-P$70-PadP$31)") (class "Default")
      (node (ref "JX2") (pin "P$31") (pinfunction "P$70_P$31") (pintype "bidirectional"))
    )
    (net (code "157") (name "unconnected-(JX2-P$73-PadP$28)") (class "Default")
      (node (ref "JX2") (pin "P$28") (pinfunction "P$73_P$28") (pintype "bidirectional"))
    )
    (net (code "158") (name "unconnected-(JX2-P$74-PadP$27)") (class "Default")
      (node (ref "JX2") (pin "P$27") (pinfunction "P$74_P$27") (pintype "bidirectional"))
    )
    (net (code "159") (name "unconnected-(JX2-P$75-PadP$26)") (class "Default")
      (node (ref "JX2") (pin "P$26") (pinfunction "P$75_P$26") (pintype "bidirectional"))
    )
    (net (code "160") (name "unconnected-(JX2-P$76-PadP$25)") (class "Default")
      (node (ref "JX2") (pin "P$25") (pinfunction "P$76_P$25") (pintype "bidirectional"))
    )
    (net (code "161") (name "unconnected-(JX2-P$81-PadP$20)") (class "Default")
      (node (ref "JX2") (pin "P$20") (pinfunction "P$81_P$20") (pintype "bidirectional"))
    )
    (net (code "162") (name "unconnected-(JX2-P$82-PadP$19)") (class "Default")
      (node (ref "JX2") (pin "P$19") (pinfunction "P$82_P$19") (pintype "bidirectional"))
    )
    (net (code "163") (name "unconnected-(JX2-P$83-PadP$18)") (class "Default")
      (node (ref "JX2") (pin "P$18") (pinfunction "P$83_P$18") (pintype "bidirectional"))
    )
    (net (code "164") (name "unconnected-(JX2-P$84-PadP$17)") (class "Default")
      (node (ref "JX2") (pin "P$17") (pinfunction "P$84_P$17") (pintype "bidirectional"))
    )
    (net (code "165") (name "unconnected-(JX2-P$87-PadP$14)") (class "Default")
      (node (ref "JX2") (pin "P$14") (pinfunction "P$87_P$14") (pintype "bidirectional"))
    )
    (net (code "166") (name "unconnected-(JX2-P$88-PadP$13)") (class "Default")
      (node (ref "JX2") (pin "P$13") (pinfunction "P$88_P$13") (pintype "bidirectional"))
    )
    (net (code "167") (name "unconnected-(JX2-P$89-PadP$12)") (class "Default")
      (node (ref "JX2") (pin "P$12") (pinfunction "P$89_P$12") (pintype "bidirectional"))
    )
    (net (code "168") (name "unconnected-(JX2-P$90-PadP$11)") (class "Default")
      (node (ref "JX2") (pin "P$11") (pinfunction "P$90_P$11") (pintype "bidirectional"))
    )
    (net (code "169") (name "unconnected-(JX2-P$93-PadP$8)") (class "Default")
      (node (ref "JX2") (pin "P$8") (pinfunction "P$93_P$8") (pintype "bidirectional"))
    )
    (net (code "170") (name "unconnected-(JX2-P$94-PadP$7)") (class "Default")
      (node (ref "JX2") (pin "P$7") (pinfunction "P$94_P$7") (pintype "bidirectional"))
    )
    (net (code "171") (name "unconnected-(JX2-P$95-PadP$6)") (class "Default")
      (node (ref "JX2") (pin "P$6") (pinfunction "P$95_P$6") (pintype "bidirectional"))
    )
    (net (code "172") (name "unconnected-(JX2-P$96-PadP$5)") (class "Default")
      (node (ref "JX2") (pin "P$5") (pinfunction "P$96_P$5") (pintype "bidirectional"))
    )
    (net (code "173") (name "unconnected-(JX2-P$97-PadP$4)") (class "Default")
      (node (ref "JX2") (pin "P$4") (pinfunction "P$97_P$4") (pintype "bidirectional"))
    )
    (net (code "174") (name "unconnected-(JX2-P$98-PadP$3)") (class "Default")
      (node (ref "JX2") (pin "P$3") (pinfunction "P$98_P$3") (pintype "bidirectional"))
    )
    (net (code "175") (name "unconnected-(JX2-P$99-PadP$2)") (class "Default")
      (node (ref "JX2") (pin "P$2") (pinfunction "P$99_P$2") (pintype "bidirectional"))
    )
    (net (code "176") (name "unconnected-(JX2-P$100-PadP$1)") (class "Default")
      (node (ref "JX2") (pin "P$1") (pinfunction "P$100_P$1") (pintype "bidirectional"))
    )
    (net (code "177") (name "unconnected-(R10-Pad1)") (class "Default")
      (node (ref "R10") (pin "1") (pinfunction "1_1") (pintype "passive"))
    )
    (net (code "178") (name "unconnected-(R10-Pad2)") (class "Default")
      (node (ref "R10") (pin "2") (pinfunction "2_2") (pintype "passive"))
    )
    (net (code "179") (name "unconnected-(R11-Pad1)") (class "Default")
      (node (ref "R11") (pin "1") (pinfunction "1_1") (pintype "passive"))
    )
    (net (code "180") (name "unconnected-(U$2-D-Pad3)") (class "Default")
      (node (ref "U$2") (pin "3") (pinfunction "D_3") (pintype "passive"))
    )
    (net (code "181") (name "unconnected-(U$2-S-Pad2)") (class "Default")
      (node (ref "U$2") (pin "2") (pinfunction "S_2") (pintype "passive"))
    )
    (net (code "182") (name "unconnected-(U$5-~{CLK}-PadP$5)") (class "Default")
      (node (ref "U$5") (pin "P$5") (pinfunction "~{CLK}_P$5") (pintype "bidirectional"))
    )
  )
)
